# single_board_voice_changer.net
KiCad netlist of a schematic drawn in EAGLE
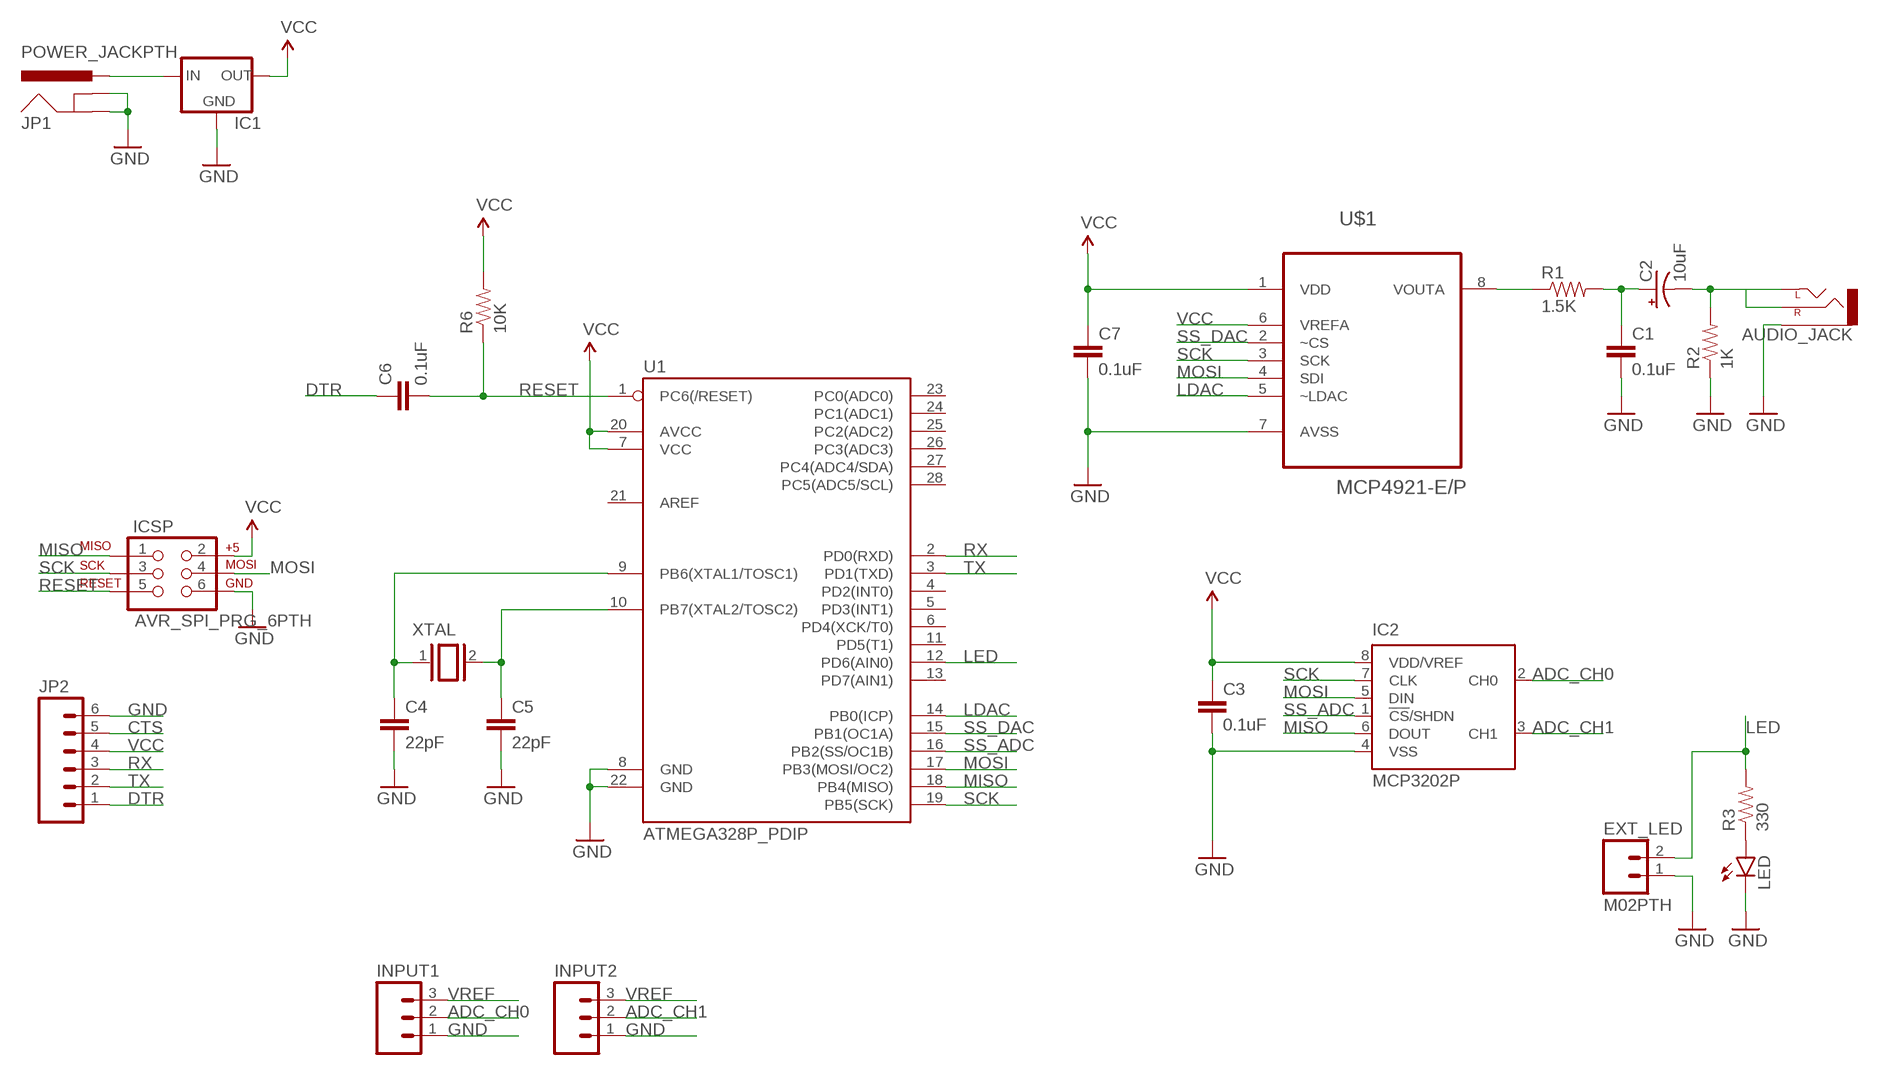
[diagram p0: schematic, sheet 1]

(export (version "E")
  (design (tool "Eeschema 10.0.6"))
  (components
    (comp (ref "AUDIO_JACK")
      (value "AUDIO-JACKPTH")
      (footprint "eagle-import:AUDIO-JACK")
      (libsource (lib "eagle-import") (part "AUDIO-JACKPTH"))
    )
    (comp (ref "C1")
      (value "0.1uF")
      (footprint "eagle-import:CAP-PTH-SMALL")
      (libsource (lib "eagle-import") (part "SparkFun-Passives_CAPPTH"))
    )
    (comp (ref "C2")
      (value "10uF")
      (footprint "eagle-import:CPOL-RADIAL-10UF-25V")
      (libsource (lib "eagle-import") (part "CAP_POLPTH2"))
    )
    (comp (ref "C3")
      (value "0.1uF")
      (footprint "eagle-import:CAP-PTH-SMALL")
      (libsource (lib "eagle-import") (part "SparkFun-Passives_CAPPTH"))
    )
    (comp (ref "C4")
      (value "22pF")
      (footprint "eagle-import:CAP-PTH-SMALL")
      (libsource (lib "eagle-import") (part "SparkFun-Passives_CAPPTH"))
    )
    (comp (ref "C5")
      (value "22pF")
      (footprint "eagle-import:CAP-PTH-SMALL")
      (libsource (lib "eagle-import") (part "SparkFun-Passives_CAPPTH"))
    )
    (comp (ref "C6")
      (value "0.1uF")
      (footprint "eagle-import:CAP-PTH-SMALL")
      (libsource (lib "eagle-import") (part "CAPPTH"))
    )
    (comp (ref "C7")
      (value "0.1uF")
      (footprint "eagle-import:CAP-PTH-SMALL")
      (libsource (lib "eagle-import") (part "SparkFun-Passives_CAPPTH"))
    )
    (comp (ref "EXT_LED")
      (value "M02PTH")
      (footprint "eagle-import:1X02")
      (libsource (lib "eagle-import") (part "M02PTH"))
    )
    (comp (ref "IC1")
      (value "V_REG_78XXSIDE")
      (footprint "eagle-import:78XXL")
      (libsource (lib "eagle-import") (part "V_REG_78XXSIDE"))
    )
    (comp (ref "IC2")
      (value "MCP3202P")
      (footprint "eagle-import:DIL8")
      (fields (field (name "MF") "MICROCHIP") (field (name "MPN") "MCP3202-CI/P"))
      (libsource (lib "eagle-import") (part "MCP3202P"))
    )
    (comp (ref "ICSP")
      (value "AVR_SPI_PRG_6PTH")
      (footprint "eagle-import:2X3")
      (libsource (lib "eagle-import") (part "AVR_SPI_PRG_6PTH"))
    )
    (comp (ref "INPUT1")
      (value "M03PTH")
      (footprint "eagle-import:1X03")
      (libsource (lib "eagle-import") (part "M03PTH"))
    )
    (comp (ref "INPUT2")
      (value "M03PTH")
      (footprint "eagle-import:1X03")
      (libsource (lib "eagle-import") (part "M03PTH"))
    )
    (comp (ref "JP1")
      (value "POWER_JACKPTH")
      (footprint "eagle-import:POWER_JACK_PTH")
      (libsource (lib "eagle-import") (part "POWER_JACKPTH"))
    )
    (comp (ref "JP2")
      (value "M06SILK_FEMALE_PTH")
      (footprint "eagle-import:1X06")
      (libsource (lib "eagle-import") (part "M06SILK_FEMALE_PTH"))
    )
    (comp (ref "LED")
      (value "LED5MM")
      (footprint "eagle-import:LED5MM")
      (libsource (lib "eagle-import") (part "LED5MM"))
    )
    (comp (ref "R1")
      (value "1.5K")
      (footprint "eagle-import:AXIAL-0.4")
      (libsource (lib "eagle-import") (part "RESISTORPTH-1/4W"))
    )
    (comp (ref "R2")
      (value "1K")
      (footprint "eagle-import:AXIAL-0.4")
      (libsource (lib "eagle-import") (part "RESISTORPTH-1/4W"))
    )
    (comp (ref "R3")
      (value "330")
      (footprint "eagle-import:AXIAL-0.4")
      (libsource (lib "eagle-import") (part "RESISTORPTH-1/4W"))
    )
    (comp (ref "R6")
      (value "10K")
      (footprint "eagle-import:AXIAL-0.4")
      (libsource (lib "eagle-import") (part "RESISTORPTH-1/4W"))
    )
    (comp (ref "U$1")
      (value "MCP4921-E/P")
      (footprint "eagle-import:DIP254P762X432-8")
      (libsource (lib "eagle-import") (part "MCP4921-E/P"))
    )
    (comp (ref "U1")
      (value "ATMEGA328P_PDIP")
      (footprint "eagle-import:DIL28-3")
      (libsource (lib "eagle-import") (part "ATMEGA328P_PDIP"))
    )
    (comp (ref "XTAL")
      (value "XTAL/S")
      (footprint "eagle-import:QS")
      (libsource (lib "eagle-import") (part "XTAL/S"))
    )
  )
  (nets
    (net (code "1") (name "/ADC_CH0") (class "Default")
      (node (ref "IC2") (pin "2") (pinfunction "CH0_2") (pintype "input"))
      (node (ref "INPUT1") (pin "2") (pinfunction "2_2") (pintype "passive"))
    )
    (net (code "2") (name "/ADC_CH1") (class "Default")
      (node (ref "IC2") (pin "3") (pinfunction "CH1_3") (pintype "input"))
      (node (ref "INPUT2") (pin "2") (pinfunction "2_2") (pintype "passive"))
    )
    (net (code "3") (name "/CTS") (class "Default")
      (node (ref "JP2") (pin "5") (pinfunction "5_5") (pintype "passive"))
    )
    (net (code "4") (name "/DTR") (class "Default")
      (node (ref "C6") (pin "1") (pinfunction "1_1") (pintype "passive"))
      (node (ref "JP2") (pin "1") (pinfunction "1_1") (pintype "passive"))
    )
    (net (code "5") (name "/LDAC") (class "Default")
      (node (ref "U$1") (pin "5") (pinfunction "~{LDAC}_5") (pintype "input"))
      (node (ref "U1") (pin "14") (pinfunction "PB0(ICP)_14") (pintype "bidirectional"))
    )
    (net (code "6") (name "/LED") (class "Default")
      (node (ref "EXT_LED") (pin "2") (pinfunction "2_2") (pintype "passive"))
      (node (ref "R3") (pin "P$2") (pinfunction "2_P$2") (pintype "passive"))
      (node (ref "U1") (pin "12") (pinfunction "PD6(AIN0)_12") (pintype "bidirectional"))
    )
    (net (code "7") (name "/MISO") (class "Default")
      (node (ref "IC2") (pin "6") (pinfunction "DOUT_6") (pintype "input"))
      (node (ref "ICSP") (pin "1") (pinfunction "1_1") (pintype "passive"))
      (node (ref "U1") (pin "18") (pinfunction "PB4(MISO)_18") (pintype "bidirectional"))
    )
    (net (code "8") (name "/MOSI") (class "Default")
      (node (ref "IC2") (pin "5") (pinfunction "DIN_5") (pintype "input"))
      (node (ref "ICSP") (pin "4") (pinfunction "4_4") (pintype "passive"))
      (node (ref "U$1") (pin "4") (pinfunction "SDI_4") (pintype "input"))
      (node (ref "U1") (pin "17") (pinfunction "PB3(MOSI/OC2)_17") (pintype "bidirectional"))
    )
    (net (code "9") (name "/RESET") (class "Default")
      (node (ref "C6") (pin "2") (pinfunction "2_2") (pintype "passive"))
      (node (ref "ICSP") (pin "5") (pinfunction "5_5") (pintype "passive"))
      (node (ref "R6") (pin "P$1") (pinfunction "1_P$1") (pintype "passive"))
      (node (ref "U1") (pin "1") (pinfunction "PC6(/RESET)_1") (pintype "bidirectional"))
    )
    (net (code "10") (name "/RX") (class "Default")
      (node (ref "JP2") (pin "3") (pinfunction "3_3") (pintype "passive"))
      (node (ref "U1") (pin "2") (pinfunction "PD0(RXD)_2") (pintype "bidirectional"))
    )
    (net (code "11") (name "/SCK") (class "Default")
      (node (ref "IC2") (pin "7") (pinfunction "CLK_7") (pintype "input"))
      (node (ref "ICSP") (pin "3") (pinfunction "3_3") (pintype "passive"))
      (node (ref "U$1") (pin "3") (pinfunction "SCK_3") (pintype "input"))
      (node (ref "U1") (pin "19") (pinfunction "PB5(SCK)_19") (pintype "bidirectional"))
    )
    (net (code "12") (name "/SS_ADC") (class "Default")
      (node (ref "IC2") (pin "1") (pinfunction "~{CS}/SHDN_1") (pintype "input"))
      (node (ref "U1") (pin "16") (pinfunction "PB2(SS/OC1B)_16") (pintype "bidirectional"))
    )
    (net (code "13") (name "/SS_DAC") (class "Default")
      (node (ref "U$1") (pin "2") (pinfunction "~{CS}_2") (pintype "input"))
      (node (ref "U1") (pin "15") (pinfunction "PB1(OC1A)_15") (pintype "bidirectional"))
    )
    (net (code "14") (name "/TX") (class "Default")
      (node (ref "JP2") (pin "2") (pinfunction "2_2") (pintype "passive"))
      (node (ref "U1") (pin "3") (pinfunction "PD1(TXD)_3") (pintype "bidirectional"))
    )
    (net (code "15") (name "/VREF") (class "Default")
      (node (ref "INPUT1") (pin "3") (pinfunction "3_3") (pintype "passive"))
      (node (ref "INPUT2") (pin "3") (pinfunction "3_3") (pintype "passive"))
    )
    (net (code "16") (name "GND") (class "Default")
      (node (ref "AUDIO_JACK") (pin "SLEEVE") (pinfunction "SLEEVE_SLEEVE") (pintype "bidirectional"))
      (node (ref "C1") (pin "2") (pinfunction "2_2") (pintype "passive"))
      (node (ref "C3") (pin "2") (pinfunction "2_2") (pintype "passive"))
      (node (ref "C4") (pin "2") (pinfunction "2_2") (pintype "passive"))
      (node (ref "C5") (pin "2") (pinfunction "2_2") (pintype "passive"))
      (node (ref "C7") (pin "2") (pinfunction "2_2") (pintype "passive"))
      (node (ref "EXT_LED") (pin "1") (pinfunction "1_1") (pintype "passive"))
      (node (ref "IC1") (pin "GND") (pinfunction "GND_GND") (pintype "input"))
      (node (ref "IC2") (pin "4") (pinfunction "VSS_4") (pintype "input"))
      (node (ref "ICSP") (pin "6") (pinfunction "6_6") (pintype "passive"))
      (node (ref "INPUT1") (pin "1") (pinfunction "1_1") (pintype "passive"))
      (node (ref "INPUT2") (pin "1") (pinfunction "1_1") (pintype "passive"))
      (node (ref "JP1") (pin "GND") (pinfunction "GND_GND") (pintype "bidirectional"))
      (node (ref "JP1") (pin "GNDBREAK") (pinfunction "GNDBREAK_GNDBREAK") (pintype "bidirectional"))
      (node (ref "JP2") (pin "6") (pinfunction "6_6") (pintype "passive"))
      (node (ref "LED") (pin "K") (pinfunction "C_K") (pintype "passive"))
      (node (ref "R2") (pin "P$1") (pinfunction "1_P$1") (pintype "passive"))
      (node (ref "U$1") (pin "7") (pinfunction "AVSS_7") (pintype "passive"))
      (node (ref "U1") (pin "22") (pinfunction "GND_22") (pintype "bidirectional"))
      (node (ref "U1") (pin "8") (pinfunction "GND_8") (pintype "bidirectional"))
    )
    (net (code "17") (name "Net-(AUDIO_JACK-LEFT)") (class "Default")
      (node (ref "AUDIO_JACK") (pin "RING") (pinfunction "RIGHT_RING") (pintype "bidirectional"))
      (node (ref "AUDIO_JACK") (pin "TIP") (pinfunction "LEFT_TIP") (pintype "bidirectional"))
      (node (ref "C2") (pin "2") (pinfunction "-_2") (pintype "passive"))
      (node (ref "R2") (pin "P$2") (pinfunction "2_P$2") (pintype "passive"))
    )
    (net (code "18") (name "Net-(C2-+)") (class "Default")
      (node (ref "C1") (pin "1") (pinfunction "1_1") (pintype "passive"))
      (node (ref "C2") (pin "1") (pinfunction "+_1") (pintype "passive"))
      (node (ref "R1") (pin "P$2") (pinfunction "2_P$2") (pintype "passive"))
    )
    (net (code "19") (name "Net-(IC1-PadIN)") (class "Default")
      (node (ref "IC1") (pin "IN") (pinfunction "IN_IN") (pintype "input"))
      (node (ref "JP1") (pin "PWR") (pinfunction "PWR_PWR") (pintype "bidirectional"))
    )
    (net (code "20") (name "Net-(R1-1)") (class "Default")
      (node (ref "R1") (pin "P$1") (pinfunction "1_P$1") (pintype "passive"))
      (node (ref "U$1") (pin "8") (pinfunction "VOUTA_8") (pintype "output"))
    )
    (net (code "21") (name "Net-(R3-1)") (class "Default")
      (node (ref "LED") (pin "A") (pinfunction "A_A") (pintype "passive"))
      (node (ref "R3") (pin "P$1") (pinfunction "1_P$1") (pintype "passive"))
    )
    (net (code "22") (name "Net-(U1-PB6(XTAL1{slash}TOSC1))") (class "Default")
      (node (ref "C4") (pin "1") (pinfunction "1_1") (pintype "passive"))
      (node (ref "U1") (pin "9") (pinfunction "PB6(XTAL1/TOSC1)_9") (pintype "bidirectional"))
      (node (ref "XTAL") (pin "1") (pinfunction "1_1") (pintype "passive"))
    )
    (net (code "23") (name "Net-(U1-PB7(XTAL2{slash}TOSC2))") (class "Default")
      (node (ref "C5") (pin "1") (pinfunction "1_1") (pintype "passive"))
      (node (ref "U1") (pin "10") (pinfunction "PB7(XTAL2/TOSC2)_10") (pintype "bidirectional"))
      (node (ref "XTAL") (pin "2") (pinfunction "2_2") (pintype "passive"))
    )
    (net (code "24") (name "VCC") (class "Default")
      (node (ref "C3") (pin "1") (pinfunction "1_1") (pintype "passive"))
      (node (ref "C7") (pin "1") (pinfunction "1_1") (pintype "passive"))
      (node (ref "IC1") (pin "OUT") (pinfunction "OUT_OUT") (pintype "output"))
      (node (ref "IC2") (pin "8") (pinfunction "VDD/VREF_8") (pintype "input"))
      (node (ref "ICSP") (pin "2") (pinfunction "2_2") (pintype "passive"))
      (node (ref "JP2") (pin "4") (pinfunction "4_4") (pintype "passive"))
      (node (ref "R6") (pin "P$2") (pinfunction "2_P$2") (pintype "passive"))
      (node (ref "U$1") (pin "1") (pinfunction "VDD_1") (pintype "power_in"))
      (node (ref "U$1") (pin "6") (pinfunction "VREFA_6") (pintype "input"))
      (node (ref "U1") (pin "20") (pinfunction "AVCC_20") (pintype "bidirectional"))
      (node (ref "U1") (pin "7") (pinfunction "VCC_7") (pintype "bidirectional"))
    )
    (net (code "25") (name "unconnected-(U1-AREF-Pad21)") (class "Default")
      (node (ref "U1") (pin "21") (pinfunction "AREF_21") (pintype "bidirectional"))
    )
    (net (code "26") (name "unconnected-(U1-PC0(ADC0)-Pad23)") (class "Default")
      (node (ref "U1") (pin "23") (pinfunction "PC0(ADC0)_23") (pintype "bidirectional"))
    )
    (net (code "27") (name "unconnected-(U1-PC1(ADC1)-Pad24)") (class "Default")
      (node (ref "U1") (pin "24") (pinfunction "PC1(ADC1)_24") (pintype "bidirectional"))
    )
    (net (code "28") (name "unconnected-(U1-PC2(ADC2)-Pad25)") (class "Default")
      (node (ref "U1") (pin "25") (pinfunction "PC2(ADC2)_25") (pintype "bidirectional"))
    )
    (net (code "29") (name "unconnected-(U1-PC3(ADC3)-Pad26)") (class "Default")
      (node (ref "U1") (pin "26") (pinfunction "PC3(ADC3)_26") (pintype "bidirectional"))
    )
    (net (code "30") (name "unconnected-(U1-PC4(ADC4{slash}SDA)-Pad27)") (class "Default")
      (node (ref "U1") (pin "27") (pinfunction "PC4(ADC4/SDA)_27") (pintype "bidirectional"))
    )
    (net (code "31") (name "unconnected-(U1-PC5(ADC5{slash}SCL)-Pad28)") (class "Default")
      (node (ref "U1") (pin "28") (pinfunction "PC5(ADC5/SCL)_28") (pintype "bidirectional"))
    )
    (net (code "32") (name "unconnected-(U1-PD2(INT0)-Pad4)") (class "Default")
      (node (ref "U1") (pin "4") (pinfunction "PD2(INT0)_4") (pintype "bidirectional"))
    )
    (net (code "33") (name "unconnected-(U1-PD3(INT1)-Pad5)") (class "Default")
      (node (ref "U1") (pin "5") (pinfunction "PD3(INT1)_5") (pintype "bidirectional"))
    )
    (net (code "34") (name "unconnected-(U1-PD4(XCK{slash}T0)-Pad6)") (class "Default")
      (node (ref "U1") (pin "6") (pinfunction "PD4(XCK/T0)_6") (pintype "bidirectional"))
    )
    (net (code "35") (name "unconnected-(U1-PD5(T1)-Pad11)") (class "Default")
      (node (ref "U1") (pin "11") (pinfunction "PD5(T1)_11") (pintype "bidirectional"))
    )
    (net (code "36") (name "unconnected-(U1-PD7(AIN1)-Pad13)") (class "Default")
      (node (ref "U1") (pin "13") (pinfunction "PD7(AIN1)_13") (pintype "bidirectional"))
    )
  )
)
